# ac_mk2.net
KiCad netlist of a schematic drawn in EAGLE
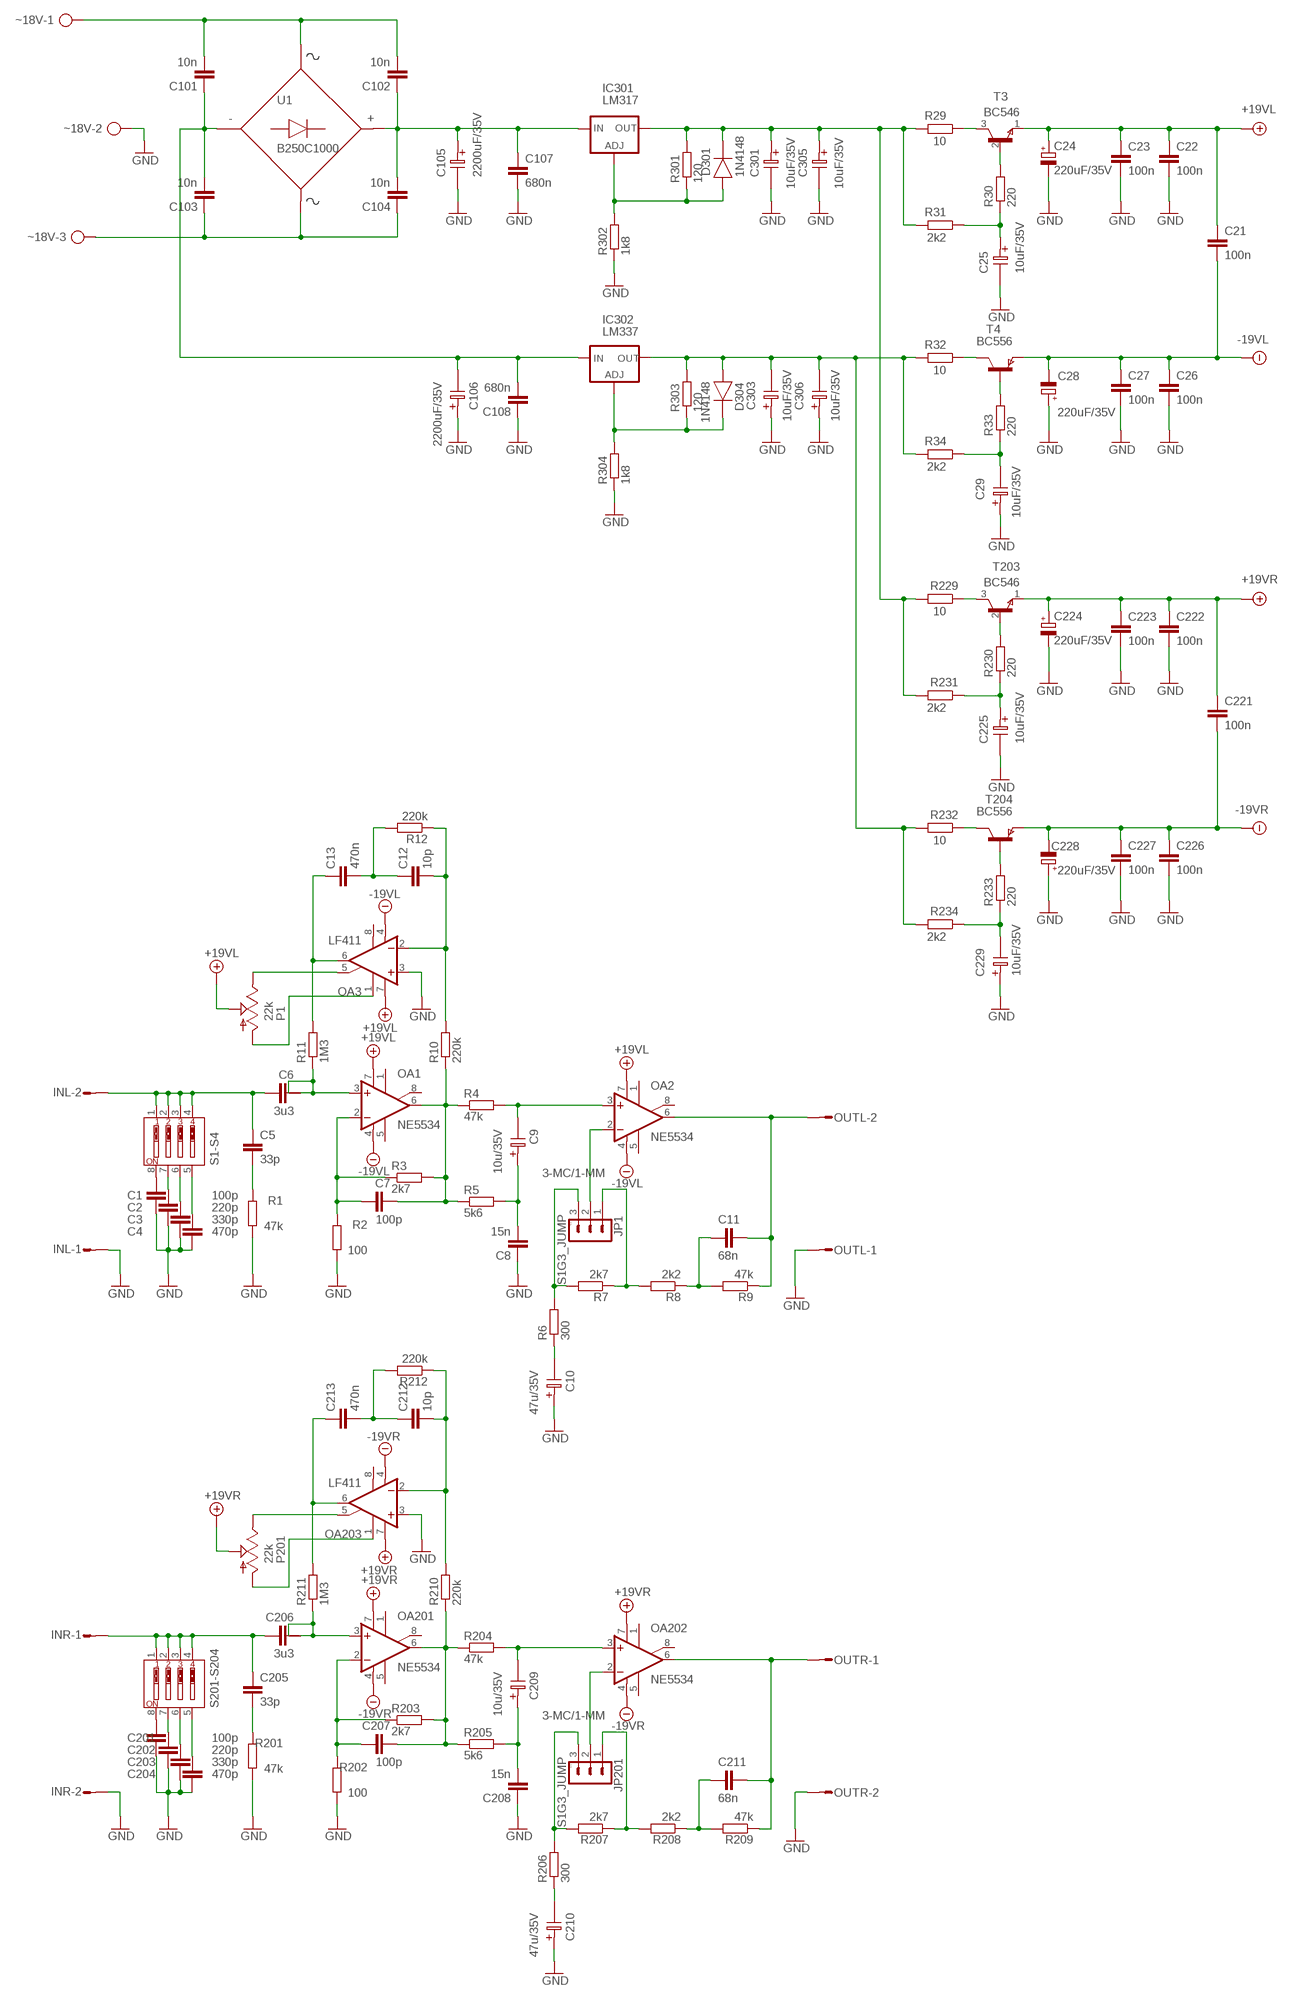
[diagram p0: schematic, sheet 1]

(export (version "E")
  (design (tool "Eeschema 10.0.6"))
  (components
    (comp (ref "C1")
      (value "100p")
      (footprint "eagle-import:C5B3.5")
      (libsource (lib "eagle-import") (part "C5/3.5"))
    )
    (comp (ref "C2")
      (value "220p")
      (footprint "eagle-import:C5B3.5")
      (libsource (lib "eagle-import") (part "C5/3.5"))
    )
    (comp (ref "C3")
      (value "330p")
      (footprint "eagle-import:C5B3.5")
      (libsource (lib "eagle-import") (part "C5/3.5"))
    )
    (comp (ref "C4")
      (value "470p")
      (footprint "eagle-import:C5B3.5")
      (libsource (lib "eagle-import") (part "C5/3.5"))
    )
    (comp (ref "C5")
      (value "33p")
      (footprint "eagle-import:KERAMICKY_RM5")
      (libsource (lib "eagle-import") (part "KERAMICKYRM5"))
    )
    (comp (ref "C6")
      (value "3u3")
      (footprint "eagle-import:C10-15B6")
      (libsource (lib "eagle-import") (part "C-10-15/6"))
    )
    (comp (ref "C7")
      (value "100p")
      (footprint "eagle-import:C5B3.5")
      (libsource (lib "eagle-import") (part "C5/3.5"))
    )
    (comp (ref "C8")
      (value "15n")
      (footprint "eagle-import:C5B3.5")
      (libsource (lib "eagle-import") (part "C5/3.5"))
    )
    (comp (ref "C9")
      (value "10u/35V")
      (footprint "eagle-import:CT07")
      (libsource (lib "eagle-import") (part "CT07"))
    )
    (comp (ref "C10")
      (value "47u/35V")
      (footprint "eagle-import:CT07")
      (libsource (lib "eagle-import") (part "CT07"))
    )
    (comp (ref "C11")
      (value "68n")
      (footprint "eagle-import:C5B3.5")
      (libsource (lib "eagle-import") (part "C5/3.5"))
    )
    (comp (ref "C12")
      (value "10p")
      (footprint "eagle-import:KERAMICKY_RM5")
      (libsource (lib "eagle-import") (part "KERAMICKYRM5"))
    )
    (comp (ref "C13")
      (value "470n")
      (footprint "eagle-import:C5B5.5")
      (libsource (lib "eagle-import") (part "C5/5.5"))
    )
    (comp (ref "C21")
      (value "100n")
      (footprint "eagle-import:C5B3.5")
      (libsource (lib "eagle-import") (part "C5/3.5"))
    )
    (comp (ref "C22")
      (value "100n")
      (footprint "eagle-import:C5B3.5")
      (libsource (lib "eagle-import") (part "C5/3.5"))
    )
    (comp (ref "C23")
      (value "100n")
      (footprint "eagle-import:C5B3.5")
      (libsource (lib "eagle-import") (part "C5/3.5"))
    )
    (comp (ref "C24")
      (value "220uF/35V")
      (footprint "eagle-import:ELEKTROLITICKY_RM3,5-8")
      (libsource (lib "eagle-import") (part "ELEKTROLITICKYRM3,5-8"))
    )
    (comp (ref "C25")
      (value "10uF/35V")
      (footprint "eagle-import:CT07")
      (libsource (lib "eagle-import") (part "CT07"))
    )
    (comp (ref "C26")
      (value "100n")
      (footprint "eagle-import:C5B3.5")
      (libsource (lib "eagle-import") (part "C5/3.5"))
    )
    (comp (ref "C27")
      (value "100n")
      (footprint "eagle-import:C5B3.5")
      (libsource (lib "eagle-import") (part "C5/3.5"))
    )
    (comp (ref "C28")
      (value "220uF/35V")
      (footprint "eagle-import:ELEKTROLITICKY_RM3,5-8")
      (libsource (lib "eagle-import") (part "ELEKTROLITICKYRM3,5-8"))
    )
    (comp (ref "C29")
      (value "10uF/35V")
      (footprint "eagle-import:CT07")
      (libsource (lib "eagle-import") (part "CT07"))
    )
    (comp (ref "C101")
      (value "10n")
      (footprint "eagle-import:C5B3.5")
      (libsource (lib "eagle-import") (part "C5/3.5"))
    )
    (comp (ref "C102")
      (value "10n")
      (footprint "eagle-import:C5B3.5")
      (libsource (lib "eagle-import") (part "C5/3.5"))
    )
    (comp (ref "C103")
      (value "10n")
      (footprint "eagle-import:C5B3.5")
      (libsource (lib "eagle-import") (part "C5/3.5"))
    )
    (comp (ref "C104")
      (value "10n")
      (footprint "eagle-import:C5B3.5")
      (libsource (lib "eagle-import") (part "C5/3.5"))
    )
    (comp (ref "C105")
      (value "2200uF/35V")
      (footprint "eagle-import:E160")
      (libsource (lib "eagle-import") (part "E16X25"))
    )
    (comp (ref "C106")
      (value "2200uF/35V")
      (footprint "eagle-import:E160")
      (libsource (lib "eagle-import") (part "E16X25"))
    )
    (comp (ref "C107")
      (value "680n")
      (footprint "eagle-import:C5B5.5")
      (libsource (lib "eagle-import") (part "C5/5.5"))
    )
    (comp (ref "C108")
      (value "680n")
      (footprint "eagle-import:C5B5.5")
      (libsource (lib "eagle-import") (part "C5/5.5"))
    )
    (comp (ref "C201")
      (value "100p")
      (footprint "eagle-import:C5B3.5")
      (libsource (lib "eagle-import") (part "C5/3.5"))
    )
    (comp (ref "C202")
      (value "220p")
      (footprint "eagle-import:C5B3.5")
      (libsource (lib "eagle-import") (part "C5/3.5"))
    )
    (comp (ref "C203")
      (value "330p")
      (footprint "eagle-import:C5B3.5")
      (libsource (lib "eagle-import") (part "C5/3.5"))
    )
    (comp (ref "C204")
      (value "470p")
      (footprint "eagle-import:C5B3.5")
      (libsource (lib "eagle-import") (part "C5/3.5"))
    )
    (comp (ref "C205")
      (value "33p")
      (footprint "eagle-import:KERAMICKY_RM5")
      (libsource (lib "eagle-import") (part "KERAMICKYRM5"))
    )
    (comp (ref "C206")
      (value "3u3")
      (footprint "eagle-import:C10-15B6")
      (libsource (lib "eagle-import") (part "C-10-15/6"))
    )
    (comp (ref "C207")
      (value "100p")
      (footprint "eagle-import:C5B3.5")
      (libsource (lib "eagle-import") (part "C5/3.5"))
    )
    (comp (ref "C208")
      (value "15n")
      (footprint "eagle-import:C5B3.5")
      (libsource (lib "eagle-import") (part "C5/3.5"))
    )
    (comp (ref "C209")
      (value "10u/35V")
      (footprint "eagle-import:CT07")
      (libsource (lib "eagle-import") (part "CT07"))
    )
    (comp (ref "C210")
      (value "47u/35V")
      (footprint "eagle-import:CT07")
      (libsource (lib "eagle-import") (part "CT07"))
    )
    (comp (ref "C211")
      (value "68n")
      (footprint "eagle-import:C5B3.5")
      (libsource (lib "eagle-import") (part "C5/3.5"))
    )
    (comp (ref "C212")
      (value "10p")
      (footprint "eagle-import:KERAMICKY_RM5")
      (libsource (lib "eagle-import") (part "KERAMICKYRM5"))
    )
    (comp (ref "C213")
      (value "470n")
      (footprint "eagle-import:C5B5.5")
      (libsource (lib "eagle-import") (part "C5/5.5"))
    )
    (comp (ref "C221")
      (value "100n")
      (footprint "eagle-import:C5B3.5")
      (libsource (lib "eagle-import") (part "C5/3.5"))
    )
    (comp (ref "C222")
      (value "100n")
      (footprint "eagle-import:C5B3.5")
      (libsource (lib "eagle-import") (part "C5/3.5"))
    )
    (comp (ref "C223")
      (value "100n")
      (footprint "eagle-import:C5B3.5")
      (libsource (lib "eagle-import") (part "C5/3.5"))
    )
    (comp (ref "C224")
      (value "220uF/35V")
      (footprint "eagle-import:ELEKTROLITICKY_RM3,5-8")
      (libsource (lib "eagle-import") (part "ELEKTROLITICKYRM3,5-8"))
    )
    (comp (ref "C225")
      (value "10uF/35V")
      (footprint "eagle-import:CT07")
      (libsource (lib "eagle-import") (part "CT07"))
    )
    (comp (ref "C226")
      (value "100n")
      (footprint "eagle-import:C5B3.5")
      (libsource (lib "eagle-import") (part "C5/3.5"))
    )
    (comp (ref "C227")
      (value "100n")
      (footprint "eagle-import:C5B3.5")
      (libsource (lib "eagle-import") (part "C5/3.5"))
    )
    (comp (ref "C228")
      (value "220uF/35V")
      (footprint "eagle-import:ELEKTROLITICKY_RM3,5-8")
      (libsource (lib "eagle-import") (part "ELEKTROLITICKYRM3,5-8"))
    )
    (comp (ref "C229")
      (value "10uF/35V")
      (footprint "eagle-import:CT07")
      (libsource (lib "eagle-import") (part "CT07"))
    )
    (comp (ref "C301")
      (value "10uF/35V")
      (footprint "eagle-import:CT07")
      (libsource (lib "eagle-import") (part "CT07"))
    )
    (comp (ref "C303")
      (value "10uF/35V")
      (footprint "eagle-import:CT07")
      (libsource (lib "eagle-import") (part "CT07"))
    )
    (comp (ref "C305")
      (value "10uF/35V")
      (footprint "eagle-import:CT07")
      (libsource (lib "eagle-import") (part "CT07"))
    )
    (comp (ref "C306")
      (value "10uF/35V")
      (footprint "eagle-import:CT07")
      (libsource (lib "eagle-import") (part "CT07"))
    )
    (comp (ref "D301")
      (value "1N4148")
      (footprint "eagle-import:DO41")
      (libsource (lib "eagle-import") (part "1N4148"))
    )
    (comp (ref "D304")
      (value "1N4148")
      (footprint "eagle-import:DO41")
      (libsource (lib "eagle-import") (part "1N4148"))
    )
    (comp (ref "IC301")
      (value "LM317")
      (footprint "eagle-import:317TS")
      (libsource (lib "eagle-import") (part "LM317TS"))
    )
    (comp (ref "IC302")
      (value "LM337")
      (footprint "eagle-import:337TS")
      (libsource (lib "eagle-import") (part "LM337TS"))
    )
    (comp (ref "INL")
      (value "S02P")
      (footprint "eagle-import:S02P")
      (libsource (lib "eagle-import") (part "S02P"))
    )
    (comp (ref "INR")
      (value "S02P")
      (footprint "eagle-import:S02P")
      (libsource (lib "eagle-import") (part "S02P"))
    )
    (comp (ref "JP1")
      (value "S1G3_JUMP")
      (footprint "eagle-import:S1G3_JUM")
      (libsource (lib "eagle-import") (part "S1G3_JUMP"))
    )
    (comp (ref "JP201")
      (value "S1G3_JUMP")
      (footprint "eagle-import:S1G3_JUM")
      (libsource (lib "eagle-import") (part "S1G3_JUMP"))
    )
    (comp (ref "OA1")
      (value "NE5534")
      (footprint "eagle-import:DIL08")
      (libsource (lib "eagle-import") (part "NE5534N"))
    )
    (comp (ref "OA2")
      (value "NE5534")
      (footprint "eagle-import:DIL08")
      (libsource (lib "eagle-import") (part "NE5534N"))
    )
    (comp (ref "OA3")
      (value "LF411")
      (footprint "eagle-import:DIL08")
      (libsource (lib "eagle-import") (part "LF411N"))
    )
    (comp (ref "OA201")
      (value "NE5534")
      (footprint "eagle-import:DIL08")
      (libsource (lib "eagle-import") (part "NE5534N"))
    )
    (comp (ref "OA202")
      (value "NE5534")
      (footprint "eagle-import:DIL08")
      (libsource (lib "eagle-import") (part "NE5534N"))
    )
    (comp (ref "OA203")
      (value "LF411")
      (footprint "eagle-import:DIL08")
      (libsource (lib "eagle-import") (part "LF411N"))
    )
    (comp (ref "OUTL")
      (value "S02P")
      (footprint "eagle-import:S02P")
      (libsource (lib "eagle-import") (part "S02P"))
    )
    (comp (ref "OUTR")
      (value "S02P")
      (footprint "eagle-import:S02P")
      (libsource (lib "eagle-import") (part "S02P"))
    )
    (comp (ref "P1")
      (value "22k")
      (footprint "eagle-import:S64W")
      (libsource (lib "eagle-import") (part "TRIM_US-S64W"))
    )
    (comp (ref "P201")
      (value "22k")
      (footprint "eagle-import:S64W")
      (libsource (lib "eagle-import") (part "TRIM_US-S64W"))
    )
    (comp (ref "R1")
      (value "47k")
      (footprint "eagle-import:0207_10")
      (libsource (lib "eagle-import") (part "R-EU_0207/10"))
    )
    (comp (ref "R2")
      (value "100")
      (footprint "eagle-import:0207_10")
      (libsource (lib "eagle-import") (part "R-EU_0207/10"))
    )
    (comp (ref "R3")
      (value "2k7")
      (footprint "eagle-import:0207_10")
      (libsource (lib "eagle-import") (part "R-EU_0207/10"))
    )
    (comp (ref "R4")
      (value "47k")
      (footprint "eagle-import:0207_10")
      (libsource (lib "eagle-import") (part "R-EU_0207/10"))
    )
    (comp (ref "R5")
      (value "5k6")
      (footprint "eagle-import:0207_10")
      (libsource (lib "eagle-import") (part "R-EU_0207/10"))
    )
    (comp (ref "R6")
      (value "300")
      (footprint "eagle-import:0207_10")
      (libsource (lib "eagle-import") (part "R-EU_0207/10"))
    )
    (comp (ref "R7")
      (value "2k7")
      (footprint "eagle-import:0207_10")
      (libsource (lib "eagle-import") (part "R-EU_0207/10"))
    )
    (comp (ref "R8")
      (value "2k2")
      (footprint "eagle-import:0207_10")
      (libsource (lib "eagle-import") (part "R-EU_0207/10"))
    )
    (comp (ref "R9")
      (value "47k")
      (footprint "eagle-import:0207_10")
      (libsource (lib "eagle-import") (part "R-EU_0207/10"))
    )
    (comp (ref "R10")
      (value "220k")
      (footprint "eagle-import:0207_10")
      (libsource (lib "eagle-import") (part "R-EU_0207/10"))
    )
    (comp (ref "R11")
      (value "1M3")
      (footprint "eagle-import:0207_10")
      (libsource (lib "eagle-import") (part "R-EU_0207/10"))
    )
    (comp (ref "R12")
      (value "220k")
      (footprint "eagle-import:0207_10")
      (libsource (lib "eagle-import") (part "R-EU_0207/10"))
    )
    (comp (ref "R29")
      (value "10")
      (footprint "eagle-import:0207_10")
      (libsource (lib "eagle-import") (part "R-EU_0207/10"))
    )
    (comp (ref "R30")
      (value "220")
      (footprint "eagle-import:0207_10")
      (libsource (lib "eagle-import") (part "R-EU_0207/10"))
    )
    (comp (ref "R31")
      (value "2k2")
      (footprint "eagle-import:0207_10")
      (libsource (lib "eagle-import") (part "R-EU_0207/10"))
    )
    (comp (ref "R32")
      (value "10")
      (footprint "eagle-import:0207_10")
      (libsource (lib "eagle-import") (part "R-EU_0207/10"))
    )
    (comp (ref "R33")
      (value "220")
      (footprint "eagle-import:0207_10")
      (libsource (lib "eagle-import") (part "R-EU_0207/10"))
    )
    (comp (ref "R34")
      (value "2k2")
      (footprint "eagle-import:0207_10")
      (libsource (lib "eagle-import") (part "R-EU_0207/10"))
    )
    (comp (ref "R201")
      (value "47k")
      (footprint "eagle-import:0207_10")
      (libsource (lib "eagle-import") (part "R-EU_0207/10"))
    )
    (comp (ref "R202")
      (value "100")
      (footprint "eagle-import:0207_10")
      (libsource (lib "eagle-import") (part "R-EU_0207/10"))
    )
    (comp (ref "R203")
      (value "2k7")
      (footprint "eagle-import:0207_10")
      (libsource (lib "eagle-import") (part "R-EU_0207/10"))
    )
    (comp (ref "R204")
      (value "47k")
      (footprint "eagle-import:0207_10")
      (libsource (lib "eagle-import") (part "R-EU_0207/10"))
    )
    (comp (ref "R205")
      (value "5k6")
      (footprint "eagle-import:0207_10")
      (libsource (lib "eagle-import") (part "R-EU_0207/10"))
    )
    (comp (ref "R206")
      (value "300")
      (footprint "eagle-import:0207_10")
      (libsource (lib "eagle-import") (part "R-EU_0207/10"))
    )
    (comp (ref "R207")
      (value "2k7")
      (footprint "eagle-import:0207_10")
      (libsource (lib "eagle-import") (part "R-EU_0207/10"))
    )
    (comp (ref "R208")
      (value "2k2")
      (footprint "eagle-import:0207_10")
      (libsource (lib "eagle-import") (part "R-EU_0207/10"))
    )
    (comp (ref "R209")
      (value "47k")
      (footprint "eagle-import:0207_10")
      (libsource (lib "eagle-import") (part "R-EU_0207/10"))
    )
    (comp (ref "R210")
      (value "220k")
      (footprint "eagle-import:0207_10")
      (libsource (lib "eagle-import") (part "R-EU_0207/10"))
    )
    (comp (ref "R211")
      (value "1M3")
      (footprint "eagle-import:0207_10")
      (libsource (lib "eagle-import") (part "R-EU_0207/10"))
    )
    (comp (ref "R212")
      (value "220k")
      (footprint "eagle-import:0207_10")
      (libsource (lib "eagle-import") (part "R-EU_0207/10"))
    )
    (comp (ref "R229")
      (value "10")
      (footprint "eagle-import:0207_10")
      (libsource (lib "eagle-import") (part "R-EU_0207/10"))
    )
    (comp (ref "R230")
      (value "220")
      (footprint "eagle-import:0207_10")
      (libsource (lib "eagle-import") (part "R-EU_0207/10"))
    )
    (comp (ref "R231")
      (value "2k2")
      (footprint "eagle-import:0207_10")
      (libsource (lib "eagle-import") (part "R-EU_0207/10"))
    )
    (comp (ref "R232")
      (value "10")
      (footprint "eagle-import:0207_10")
      (libsource (lib "eagle-import") (part "R-EU_0207/10"))
    )
    (comp (ref "R233")
      (value "220")
      (footprint "eagle-import:0207_10")
      (libsource (lib "eagle-import") (part "R-EU_0207/10"))
    )
    (comp (ref "R234")
      (value "2k2")
      (footprint "eagle-import:0207_10")
      (libsource (lib "eagle-import") (part "R-EU_0207/10"))
    )
    (comp (ref "R301")
      (value "120")
      (footprint "eagle-import:0207_10")
      (libsource (lib "eagle-import") (part "R-EU_0207/10"))
    )
    (comp (ref "R302")
      (value "1k8")
      (footprint "eagle-import:0207_10")
      (libsource (lib "eagle-import") (part "R-EU_0207/10"))
    )
    (comp (ref "R303")
      (value "120")
      (footprint "eagle-import:0207_10")
      (libsource (lib "eagle-import") (part "R-EU_0207/10"))
    )
    (comp (ref "R304")
      (value "1k8")
      (footprint "eagle-import:0207_10")
      (libsource (lib "eagle-import") (part "R-EU_0207/10"))
    )
    (comp (ref "S1-S4")
      (value "DIP4X")
      (footprint "eagle-import:EDG-04")
      (libsource (lib "eagle-import") (part "DIP4X"))
    )
    (comp (ref "S201-S204")
      (value "DIP4X")
      (footprint "eagle-import:EDG-04")
      (libsource (lib "eagle-import") (part "DIP4X"))
    )
    (comp (ref "T3")
      (value "BC546")
      (footprint "eagle-import:TO-92C")
      (libsource (lib "eagle-import") (part "BC546A"))
    )
    (comp (ref "T4")
      (value "BC556")
      (footprint "eagle-import:TO-92C")
      (libsource (lib "eagle-import") (part "BC556B"))
    )
    (comp (ref "T203")
      (value "BC546")
      (footprint "eagle-import:TO-92C")
      (libsource (lib "eagle-import") (part "BC546A"))
    )
    (comp (ref "T204")
      (value "BC556")
      (footprint "eagle-import:TO-92C")
      (libsource (lib "eagle-import") (part "BC556B"))
    )
    (comp (ref "U1")
      (value "B250C1000")
      (footprint "eagle-import:DB1")
      (libsource (lib "eagle-import") (part "B250C1500"))
    )
    (comp (ref "~18V")
      (value "AK500/3")
      (footprint "eagle-import:AK500_3")
      (libsource (lib "eagle-import") (part "AK500/3"))
    )
  )
  (nets
    (net (code "1") (name "+19VL") (class "Default")
      (node (ref "C21") (pin "1") (pinfunction "1_1") (pintype "passive"))
      (node (ref "C22") (pin "1") (pinfunction "1_1") (pintype "passive"))
      (node (ref "C23") (pin "1") (pinfunction "1_1") (pintype "passive"))
      (node (ref "C24") (pin "P$2") (pinfunction "+_P$2") (pintype "passive"))
      (node (ref "OA1") (pin "7") (pinfunction "V+_7") (pintype "power_in"))
      (node (ref "OA2") (pin "7") (pinfunction "V+_7") (pintype "power_in"))
      (node (ref "OA3") (pin "7") (pinfunction "V+_7") (pintype "power_in"))
      (node (ref "P1") (pin "S") (pinfunction "S_S") (pintype "passive"))
      (node (ref "T3") (pin "1") (pinfunction "E_1") (pintype "passive"))
    )
    (net (code "2") (name "+19VR") (class "Default")
      (node (ref "C221") (pin "1") (pinfunction "1_1") (pintype "passive"))
      (node (ref "C222") (pin "1") (pinfunction "1_1") (pintype "passive"))
      (node (ref "C223") (pin "1") (pinfunction "1_1") (pintype "passive"))
      (node (ref "C224") (pin "P$2") (pinfunction "+_P$2") (pintype "passive"))
      (node (ref "OA201") (pin "7") (pinfunction "V+_7") (pintype "power_in"))
      (node (ref "OA202") (pin "7") (pinfunction "V+_7") (pintype "power_in"))
      (node (ref "OA203") (pin "7") (pinfunction "V+_7") (pintype "power_in"))
      (node (ref "P201") (pin "S") (pinfunction "S_S") (pintype "passive"))
      (node (ref "T203") (pin "1") (pinfunction "E_1") (pintype "passive"))
    )
    (net (code "3") (name "-19VL") (class "Default")
      (node (ref "C21") (pin "2") (pinfunction "2_2") (pintype "passive"))
      (node (ref "C26") (pin "1") (pinfunction "1_1") (pintype "passive"))
      (node (ref "C27") (pin "1") (pinfunction "1_1") (pintype "passive"))
      (node (ref "C28") (pin "P$1") (pinfunction "-_P$1") (pintype "passive"))
      (node (ref "OA1") (pin "4") (pinfunction "V-_4") (pintype "power_in"))
      (node (ref "OA2") (pin "4") (pinfunction "V-_4") (pintype "power_in"))
      (node (ref "OA3") (pin "4") (pinfunction "V-_4") (pintype "power_in"))
      (node (ref "T4") (pin "1") (pinfunction "E_1") (pintype "passive"))
    )
    (net (code "4") (name "-19VR") (class "Default")
      (node (ref "C221") (pin "2") (pinfunction "2_2") (pintype "passive"))
      (node (ref "C226") (pin "1") (pinfunction "1_1") (pintype "passive"))
      (node (ref "C227") (pin "1") (pinfunction "1_1") (pintype "passive"))
      (node (ref "C228") (pin "P$1") (pinfunction "-_P$1") (pintype "passive"))
      (node (ref "OA201") (pin "4") (pinfunction "V-_4") (pintype "power_in"))
      (node (ref "OA202") (pin "4") (pinfunction "V-_4") (pintype "power_in"))
      (node (ref "OA203") (pin "4") (pinfunction "V-_4") (pintype "power_in"))
      (node (ref "T204") (pin "1") (pinfunction "E_1") (pintype "passive"))
    )
    (net (code "5") (name "GND") (class "Default")
      (node (ref "C1") (pin "2") (pinfunction "2_2") (pintype "passive"))
      (node (ref "C10") (pin "1") (pinfunction "1_1") (pintype "passive"))
      (node (ref "C105") (pin "2") (pinfunction "2_2") (pintype "passive"))
      (node (ref "C106") (pin "1") (pinfunction "1_1") (pintype "passive"))
      (node (ref "C107") (pin "2") (pinfunction "2_2") (pintype "passive"))
      (node (ref "C108") (pin "1") (pinfunction "1_1") (pintype "passive"))
      (node (ref "C2") (pin "2") (pinfunction "2_2") (pintype "passive"))
      (node (ref "C201") (pin "2") (pinfunction "2_2") (pintype "passive"))
      (node (ref "C202") (pin "2") (pinfunction "2_2") (pintype "passive"))
      (node (ref "C203") (pin "2") (pinfunction "2_2") (pintype "passive"))
      (node (ref "C204") (pin "2") (pinfunction "2_2") (pintype "passive"))
      (node (ref "C208") (pin "1") (pinfunction "1_1") (pintype "passive"))
      (node (ref "C210") (pin "1") (pinfunction "1_1") (pintype "passive"))
      (node (ref "C22") (pin "2") (pinfunction "2_2") (pintype "passive"))
      (node (ref "C222") (pin "2") (pinfunction "2_2") (pintype "passive"))
      (node (ref "C223") (pin "2") (pinfunction "2_2") (pintype "passive"))
      (node (ref "C224") (pin "P$1") (pinfunction "-_P$1") (pintype "passive"))
      (node (ref "C225") (pin "2") (pinfunction "2_2") (pintype "passive"))
      (node (ref "C226") (pin "2") (pinfunction "2_2") (pintype "passive"))
      (node (ref "C227") (pin "2") (pinfunction "2_2") (pintype "passive"))
      (node (ref "C228") (pin "P$2") (pinfunction "+_P$2") (pintype "passive"))
      (node (ref "C229") (pin "1") (pinfunction "1_1") (pintype "passive"))
      (node (ref "C23") (pin "2") (pinfunction "2_2") (pintype "passive"))
      (node (ref "C24") (pin "P$1") (pinfunction "-_P$1") (pintype "passive"))
      (node (ref "C25") (pin "2") (pinfunction "2_2") (pintype "passive"))
      (node (ref "C26") (pin "2") (pinfunction "2_2") (pintype "passive"))
      (node (ref "C27") (pin "2") (pinfunction "2_2") (pintype "passive"))
      (node (ref "C28") (pin "P$2") (pinfunction "+_P$2") (pintype "passive"))
      (node (ref "C29") (pin "1") (pinfunction "1_1") (pintype "passive"))
      (node (ref "C3") (pin "2") (pinfunction "2_2") (pintype "passive"))
      (node (ref "C301") (pin "2") (pinfunction "2_2") (pintype "passive"))
      (node (ref "C303") (pin "1") (pinfunction "1_1") (pintype "passive"))
      (node (ref "C305") (pin "2") (pinfunction "2_2") (pintype "passive"))
      (node (ref "C306") (pin "1") (pinfunction "1_1") (pintype "passive"))
      (node (ref "C4") (pin "2") (pinfunction "2_2") (pintype "passive"))
      (node (ref "C8") (pin "1") (pinfunction "1_1") (pintype "passive"))
      (node (ref "INL") (pin "1") (pinfunction "S_1") (pintype "passive"))
      (node (ref "INR") (pin "2") (pinfunction "S_2") (pintype "passive"))
      (node (ref "OA203") (pin "3") (pinfunction "+IN_3") (pintype "input"))
      (node (ref "OA3") (pin "3") (pinfunction "+IN_3") (pintype "input"))
      (node (ref "OUTL") (pin "1") (pinfunction "S_1") (pintype "passive"))
      (node (ref "OUTR") (pin "2") (pinfunction "S_2") (pintype "passive"))
      (node (ref "R1") (pin "1") (pinfunction "1_1") (pintype "passive"))
      (node (ref "R2") (pin "1") (pinfunction "1_1") (pintype "passive"))
      (node (ref "R201") (pin "1") (pinfunction "1_1") (pintype "passive"))
      (node (ref "R202") (pin "1") (pinfunction "1_1") (pintype "passive"))
      (node (ref "R302") (pin "1") (pinfunction "1_1") (pintype "passive"))
      (node (ref "R304") (pin "1") (pinfunction "1_1") (pintype "passive"))
      (node (ref "~18V") (pin "2") (pinfunction "KL_2") (pintype "passive"))
    )
    (net (code "6") (name "Net-(C1-Pad1)") (class "Default")
      (node (ref "C1") (pin "1") (pinfunction "1_1") (pintype "passive"))
      (node (ref "S1-S4") (pin "8") (pinfunction "8_8") (pintype "passive"))
    )
    (net (code "7") (name "Net-(C2-Pad1)") (class "Default")
      (node (ref "C2") (pin "1") (pinfunction "1_1") (pintype "passive"))
      (node (ref "S1-S4") (pin "7") (pinfunction "7_7") (pintype "passive"))
    )
    (net (code "8") (name "Net-(C3-Pad1)") (class "Default")
      (node (ref "C3") (pin "1") (pinfunction "1_1") (pintype "passive"))
      (node (ref "S1-S4") (pin "6") (pinfunction "6_6") (pintype "passive"))
    )
    (net (code "9") (name "Net-(C4-Pad1)") (class "Default")
      (node (ref "C4") (pin "1") (pinfunction "1_1") (pintype "passive"))
      (node (ref "S1-S4") (pin "5") (pinfunction "5_5") (pintype "passive"))
    )
    (net (code "10") (name "Net-(C5-1)") (class "Default")
      (node (ref "C5") (pin "P$1") (pinfunction "1_P$1") (pintype "passive"))
      (node (ref "C6") (pin "1") (pinfunction "1_1") (pintype "passive"))
      (node (ref "INL") (pin "2") (pinfunction "S_2") (pintype "passive"))
      (node (ref "S1-S4") (pin "1") (pinfunction "1_1") (pintype "passive"))
      (node (ref "S1-S4") (pin "2") (pinfunction "2_2") (pintype "passive"))
      (node (ref "S1-S4") (pin "3") (pinfunction "3_3") (pintype "passive"))
      (node (ref "S1-S4") (pin "4") (pinfunction "4_4") (pintype "passive"))
    )
    (net (code "11") (name "Net-(C5-2)") (class "Default")
      (node (ref "C5") (pin "P$2") (pinfunction "2_P$2") (pintype "passive"))
      (node (ref "R1") (pin "2") (pinfunction "2_2") (pintype "passive"))
    )
    (net (code "12") (name "Net-(C8-Pad2)") (class "Default")
      (node (ref "C8") (pin "2") (pinfunction "2_2") (pintype "passive"))
      (node (ref "C9") (pin "1") (pinfunction "1_1") (pintype "passive"))
      (node (ref "R5") (pin "2") (pinfunction "2_2") (pintype "passive"))
    )
    (net (code "13") (name "Net-(C10-Pad2)") (class "Default")
      (node (ref "C10") (pin "2") (pinfunction "2_2") (pintype "passive"))
      (node (ref "R6") (pin "1") (pinfunction "1_1") (pintype "passive"))
    )
    (net (code "14") (name "Net-(C11-Pad2)") (class "Default")
      (node (ref "C11") (pin "2") (pinfunction "2_2") (pintype "passive"))
      (node (ref "R8") (pin "1") (pinfunction "1_1") (pintype "passive"))
      (node (ref "R9") (pin "2") (pinfunction "2_2") (pintype "passive"))
    )
    (net (code "15") (name "Net-(C12-1)") (class "Default")
      (node (ref "C12") (pin "P$1") (pinfunction "1_P$1") (pintype "passive"))
      (node (ref "C13") (pin "2") (pinfunction "2_2") (pintype "passive"))
      (node (ref "R12") (pin "2") (pinfunction "2_2") (pintype "passive"))
    )
    (net (code "16") (name "Net-(C12-2)") (class "Default")
      (node (ref "C12") (pin "P$2") (pinfunction "2_P$2") (pintype "passive"))
      (node (ref "OA3") (pin "2") (pinfunction "-IN_2") (pintype "input"))
      (node (ref "R10") (pin "2") (pinfunction "2_2") (pintype "passive"))
      (node (ref "R12") (pin "1") (pinfunction "1_1") (pintype "passive"))
    )
    (net (code "17") (name "Net-(C25-Pad1)") (class "Default")
      (node (ref "C25") (pin "1") (pinfunction "1_1") (pintype "passive"))
      (node (ref "R30") (pin "1") (pinfunction "1_1") (pintype "passive"))
      (node (ref "R31") (pin "1") (pinfunction "1_1") (pintype "passive"))
    )
    (net (code "18") (name "Net-(C29-Pad2)") (class "Default")
      (node (ref "C29") (pin "2") (pinfunction "2_2") (pintype "passive"))
      (node (ref "R33") (pin "1") (pinfunction "1_1") (pintype "passive"))
      (node (ref "R34") (pin "1") (pinfunction "1_1") (pintype "passive"))
    )
    (net (code "19") (name "Net-(C201-Pad1)") (class "Default")
      (node (ref "C201") (pin "1") (pinfunction "1_1") (pintype "passive"))
      (node (ref "S201-S204") (pin "8") (pinfunction "8_8") (pintype "passive"))
    )
    (net (code "20") (name "Net-(C202-Pad1)") (class "Default")
      (node (ref "C202") (pin "1") (pinfunction "1_1") (pintype "passive"))
      (node (ref "S201-S204") (pin "7") (pinfunction "7_7") (pintype "passive"))
    )
    (net (code "21") (name "Net-(C203-Pad1)") (class "Default")
      (node (ref "C203") (pin "1") (pinfunction "1_1") (pintype "passive"))
      (node (ref "S201-S204") (pin "6") (pinfunction "6_6") (pintype "passive"))
    )
    (net (code "22") (name "Net-(C204-Pad1)") (class "Default")
      (node (ref "C204") (pin "1") (pinfunction "1_1") (pintype "passive"))
      (node (ref "S201-S204") (pin "5") (pinfunction "5_5") (pintype "passive"))
    )
    (net (code "23") (name "Net-(C205-1)") (class "Default")
      (node (ref "C205") (pin "P$1") (pinfunction "1_P$1") (pintype "passive"))
      (node (ref "C206") (pin "1") (pinfunction "1_1") (pintype "passive"))
      (node (ref "INR") (pin "1") (pinfunction "S_1") (pintype "passive"))
      (node (ref "S201-S204") (pin "1") (pinfunction "1_1") (pintype "passive"))
      (node (ref "S201-S204") (pin "2") (pinfunction "2_2") (pintype "passive"))
      (node (ref "S201-S204") (pin "3") (pinfunction "3_3") (pintype "passive"))
      (node (ref "S201-S204") (pin "4") (pinfunction "4_4") (pintype "passive"))
    )
    (net (code "24") (name "Net-(C205-2)") (class "Default")
      (node (ref "C205") (pin "P$2") (pinfunction "2_P$2") (pintype "passive"))
      (node (ref "R201") (pin "2") (pinfunction "2_2") (pintype "passive"))
    )
    (net (code "25") (name "Net-(C208-Pad2)") (class "Default")
      (node (ref "C208") (pin "2") (pinfunction "2_2") (pintype "passive"))
      (node (ref "C209") (pin "1") (pinfunction "1_1") (pintype "passive"))
      (node (ref "R205") (pin "2") (pinfunction "2_2") (pintype "passive"))
    )
    (net (code "26") (name "Net-(C210-Pad2)") (class "Default")
      (node (ref "C210") (pin "2") (pinfunction "2_2") (pintype "passive"))
      (node (ref "R206") (pin "1") (pinfunction "1_1") (pintype "passive"))
    )
    (net (code "27") (name "Net-(C211-Pad2)") (class "Default")
      (node (ref "C211") (pin "2") (pinfunction "2_2") (pintype "passive"))
      (node (ref "R208") (pin "1") (pinfunction "1_1") (pintype "passive"))
      (node (ref "R209") (pin "2") (pinfunction "2_2") (pintype "passive"))
    )
    (net (code "28") (name "Net-(C212-1)") (class "Default")
      (node (ref "C212") (pin "P$1") (pinfunction "1_P$1") (pintype "passive"))
      (node (ref "C213") (pin "2") (pinfunction "2_2") (pintype "passive"))
      (node (ref "R212") (pin "2") (pinfunction "2_2") (pintype "passive"))
    )
    (net (code "29") (name "Net-(C212-2)") (class "Default")
      (node (ref "C212") (pin "P$2") (pinfunction "2_P$2") (pintype "passive"))
      (node (ref "OA203") (pin "2") (pinfunction "-IN_2") (pintype "input"))
      (node (ref "R210") (pin "2") (pinfunction "2_2") (pintype "passive"))
      (node (ref "R212") (pin "1") (pinfunction "1_1") (pintype "passive"))
    )
    (net (code "30") (name "Net-(C225-Pad1)") (class "Default")
      (node (ref "C225") (pin "1") (pinfunction "1_1") (pintype "passive"))
      (node (ref "R230") (pin "1") (pinfunction "1_1") (pintype "passive"))
      (node (ref "R231") (pin "1") (pinfunction "1_1") (pintype "passive"))
    )
    (net (code "31") (name "Net-(C229-Pad2)") (class "Default")
      (node (ref "C229") (pin "2") (pinfunction "2_2") (pintype "passive"))
      (node (ref "R233") (pin "1") (pinfunction "1_1") (pintype "passive"))
      (node (ref "R234") (pin "1") (pinfunction "1_1") (pintype "passive"))
    )
    (net (code "32") (name "Net-(IC301-ADJ)") (class "Default")
      (node (ref "D301") (pin "A") (pinfunction "A_A") (pintype "passive"))
      (node (ref "IC301") (pin "1") (pinfunction "ADJ_1") (pintype "input"))
      (node (ref "R301") (pin "1") (pinfunction "1_1") (pintype "passive"))
      (node (ref "R302") (pin "2") (pinfunction "2_2") (pintype "passive"))
    )
    (net (code "33") (name "Net-(IC301-IN)") (class "Default")
      (node (ref "C102") (pin "1") (pinfunction "1_1") (pintype "passive"))
      (node (ref "C104") (pin "2") (pinfunction "2_2") (pintype "passive"))
      (node (ref "C105") (pin "1") (pinfunction "1_1") (pintype "passive"))
      (node (ref "C107") (pin "1") (pinfunction "1_1") (pintype "passive"))
      (node (ref "IC301") (pin "3") (pinfunction "IN_3") (pintype "input"))
      (node (ref "U1") (pin "1") (pinfunction "1_1") (pintype "passive"))
    )
    (net (code "34") (name "Net-(IC301-OUT)") (class "Default")
      (node (ref "C301") (pin "1") (pinfunction "1_1") (pintype "passive"))
      (node (ref "C305") (pin "1") (pinfunction "1_1") (pintype "passive"))
      (node (ref "D301") (pin "K") (pinfunction "K_K") (pintype "passive"))
      (node (ref "IC301") (pin "2") (pinfunction "OUT_2") (pintype "passive"))
      (node (ref "R229") (pin "2") (pinfunction "2_2") (pintype "passive"))
      (node (ref "R231") (pin "2") (pinfunction "2_2") (pintype "passive"))
      (node (ref "R29") (pin "2") (pinfunction "2_2") (pintype "passive"))
      (node (ref "R301") (pin "2") (pinfunction "2_2") (pintype "passive"))
      (node (ref "R31") (pin "2") (pinfunction "2_2") (pintype "passive"))
    )
    (net (code "35") (name "Net-(IC302-ADJ)") (class "Default")
      (node (ref "D304") (pin "K") (pinfunction "K_K") (pintype "passive"))
      (node (ref "IC302") (pin "1") (pinfunction "ADJ_1") (pintype "input"))
      (node (ref "R303") (pin "1") (pinfunction "1_1") (pintype "passive"))
      (node (ref "R304") (pin "2") (pinfunction "2_2") (pintype "passive"))
    )
    (net (code "36") (name "Net-(IC302-IN)") (class "Default")
      (node (ref "C101") (pin "1") (pinfunction "1_1") (pintype "passive"))
      (node (ref "C103") (pin "2") (pinfunction "2_2") (pintype "passive"))
      (node (ref "C106") (pin "2") (pinfunction "2_2") (pintype "passive"))
      (node (ref "C108") (pin "2") (pinfunction "2_2") (pintype "passive"))
      (node (ref "IC302") (pin "2") (pinfunction "IN_2") (pintype "input"))
      (node (ref "U1") (pin "2") (pinfunction "2_2") (pintype "passive"))
    )
    (net (code "37") (name "Net-(IC302-OUT)") (class "Default")
      (node (ref "C303") (pin "2") (pinfunction "2_2") (pintype "passive"))
      (node (ref "C306") (pin "2") (pinfunction "2_2") (pintype "passive"))
      (node (ref "D304") (pin "A") (pinfunction "A_A") (pintype "passive"))
      (node (ref "IC302") (pin "3") (pinfunction "OUT_3") (pintype "passive"))
      (node (ref "R232") (pin "2") (pinfunction "2_2") (pintype "passive"))
      (node (ref "R234") (pin "2") (pinfunction "2_2") (pintype "passive"))
      (node (ref "R303") (pin "2") (pinfunction "2_2") (pintype "passive"))
      (node (ref "R32") (pin "2") (pinfunction "2_2") (pintype "passive"))
      (node (ref "R34") (pin "2") (pinfunction "2_2") (pintype "passive"))
    )
    (net (code "38") (name "Net-(JP1-Pad1)") (class "Default")
      (node (ref "JP1") (pin "1") (pinfunction "1_1") (pintype "passive"))
      (node (ref "R7") (pin "1") (pinfunction "1_1") (pintype "passive"))
      (node (ref "R8") (pin "2") (pinfunction "2_2") (pintype "passive"))
    )
    (net (code "39") (name "Net-(JP1-Pad3)") (class "Default")
      (node (ref "JP1") (pin "3") (pinfunction "3_3") (pintype "passive"))
      (node (ref "R6") (pin "2") (pinfunction "2_2") (pintype "passive"))
      (node (ref "R7") (pin "2") (pinfunction "2_2") (pintype "passive"))
    )
    (net (code "40") (name "Net-(JP201-Pad1)") (class "Default")
      (node (ref "JP201") (pin "1") (pinfunction "1_1") (pintype "passive"))
      (node (ref "R207") (pin "1") (pinfunction "1_1") (pintype "passive"))
      (node (ref "R208") (pin "2") (pinfunction "2_2") (pintype "passive"))
    )
    (net (code "41") (name "Net-(JP201-Pad3)") (class "Default")
      (node (ref "JP201") (pin "3") (pinfunction "3_3") (pintype "passive"))
      (node (ref "R206") (pin "2") (pinfunction "2_2") (pintype "passive"))
      (node (ref "R207") (pin "2") (pinfunction "2_2") (pintype "passive"))
    )
    (net (code "42") (name "Net-(OA1-+IN)") (class "Default")
      (node (ref "C6") (pin "2") (pinfunction "2_2") (pintype "passive"))
      (node (ref "C6") (pin "3") (pinfunction "3_3") (pintype "passive"))
      (node (ref "OA1") (pin "3") (pinfunction "+IN_3") (pintype "input"))
      (node (ref "R11") (pin "1") (pinfunction "1_1") (pintype "passive"))
    )
    (net (code "43") (name "Net-(OA1--IN)") (class "Default")
      (node (ref "C7") (pin "1") (pinfunction "1_1") (pintype "passive"))
      (node (ref "OA1") (pin "2") (pinfunction "-IN_2") (pintype "input"))
      (node (ref "R2") (pin "2") (pinfunction "2_2") (pintype "passive"))
      (node (ref "R3") (pin "1") (pinfunction "1_1") (pintype "passive"))
    )
    (net (code "44") (name "Net-(OA1-OUT)") (class "Default")
      (node (ref "C7") (pin "2") (pinfunction "2_2") (pintype "passive"))
      (node (ref "OA1") (pin "6") (pinfunction "OUT_6") (pintype "output"))
      (node (ref "R10") (pin "1") (pinfunction "1_1") (pintype "passive"))
      (node (ref "R3") (pin "2") (pinfunction "2_2") (pintype "passive"))
      (node (ref "R4") (pin "1") (pinfunction "1_1") (pintype "passive"))
      (node (ref "R5") (pin "1") (pinfunction "1_1") (pintype "passive"))
    )
    (net (code "45") (name "Net-(OA2-+IN)") (class "Default")
      (node (ref "C9") (pin "2") (pinfunction "2_2") (pintype "passive"))
      (node (ref "OA2") (pin "3") (pinfunction "+IN_3") (pintype "input"))
      (node (ref "R4") (pin "2") (pinfunction "2_2") (pintype "passive"))
    )
    (net (code "46") (name "Net-(OA2--IN)") (class "Default")
      (node (ref "JP1") (pin "2") (pinfunction "2_2") (pintype "passive"))
      (node (ref "OA2") (pin "2") (pinfunction "-IN_2") (pintype "input"))
    )
    (net (code "47") (name "Net-(OA2-OUT)") (class "Default")
      (node (ref "C11") (pin "1") (pinfunction "1_1") (pintype "passive"))
      (node (ref "OA2") (pin "6") (pinfunction "OUT_6") (pintype "output"))
      (node (ref "OUTL") (pin "2") (pinfunction "S_2") (pintype "passive"))
      (node (ref "R9") (pin "1") (pinfunction "1_1") (pintype "passive"))
    )
    (net (code "48") (name "Net-(OA3-ON1)") (class "Default")
      (node (ref "OA3") (pin "1") (pinfunction "ON1_1") (pintype "passive"))
      (node (ref "P1") (pin "A") (pinfunction "A_A") (pintype "passive"))
    )
    (net (code "49") (name "Net-(OA3-ON2)") (class "Default")
      (node (ref "OA3") (pin "5") (pinfunction "ON2_5") (pintype "passive"))
      (node (ref "P1") (pin "E") (pinfunction "E_E") (pintype "passive"))
    )
    (net (code "50") (name "Net-(OA3-OUT)") (class "Default")
      (node (ref "C13") (pin "1") (pinfunction "1_1") (pintype "passive"))
      (node (ref "OA3") (pin "6") (pinfunction "OUT_6") (pintype "output"))
      (node (ref "R11") (pin "2") (pinfunction "2_2") (pintype "passive"))
    )
    (net (code "51") (name "Net-(OA201-+IN)") (class "Default")
      (node (ref "C206") (pin "2") (pinfunction "2_2") (pintype "passive"))
      (node (ref "C206") (pin "3") (pinfunction "3_3") (pintype "passive"))
      (node (ref "OA201") (pin "3") (pinfunction "+IN_3") (pintype "input"))
      (node (ref "R211") (pin "1") (pinfunction "1_1") (pintype "passive"))
    )
    (net (code "52") (name "Net-(OA201--IN)") (class "Default")
      (node (ref "C207") (pin "1") (pinfunction "1_1") (pintype "passive"))
      (node (ref "OA201") (pin "2") (pinfunction "-IN_2") (pintype "input"))
      (node (ref "R202") (pin "2") (pinfunction "2_2") (pintype "passive"))
      (node (ref "R203") (pin "1") (pinfunction "1_1") (pintype "passive"))
    )
    (net (code "53") (name "Net-(OA201-OUT)") (class "Default")
      (node (ref "C207") (pin "2") (pinfunction "2_2") (pintype "passive"))
      (node (ref "OA201") (pin "6") (pinfunction "OUT_6") (pintype "output"))
      (node (ref "R203") (pin "2") (pinfunction "2_2") (pintype "passive"))
      (node (ref "R204") (pin "1") (pinfunction "1_1") (pintype "passive"))
      (node (ref "R205") (pin "1") (pinfunction "1_1") (pintype "passive"))
      (node (ref "R210") (pin "1") (pinfunction "1_1") (pintype "passive"))
    )
    (net (code "54") (name "Net-(OA202-+IN)") (class "Default")
      (node (ref "C209") (pin "2") (pinfunction "2_2") (pintype "passive"))
      (node (ref "OA202") (pin "3") (pinfunction "+IN_3") (pintype "input"))
      (node (ref "R204") (pin "2") (pinfunction "2_2") (pintype "passive"))
    )
    (net (code "55") (name "Net-(OA202--IN)") (class "Default")
      (node (ref "JP201") (pin "2") (pinfunction "2_2") (pintype "passive"))
      (node (ref "OA202") (pin "2") (pinfunction "-IN_2") (pintype "input"))
    )
    (net (code "56") (name "Net-(OA202-OUT)") (class "Default")
      (node (ref "C211") (pin "1") (pinfunction "1_1") (pintype "passive"))
      (node (ref "OA202") (pin "6") (pinfunction "OUT_6") (pintype "output"))
      (node (ref "OUTR") (pin "1") (pinfunction "S_1") (pintype "passive"))
      (node (ref "R209") (pin "1") (pinfunction "1_1") (pintype "passive"))
    )
    (net (code "57") (name "Net-(OA203-ON1)") (class "Default")
      (node (ref "OA203") (pin "1") (pinfunction "ON1_1") (pintype "passive"))
      (node (ref "P201") (pin "A") (pinfunction "A_A") (pintype "passive"))
    )
    (net (code "58") (name "Net-(OA203-ON2)") (class "Default")
      (node (ref "OA203") (pin "5") (pinfunction "ON2_5") (pintype "passive"))
      (node (ref "P201") (pin "E") (pinfunction "E_E") (pintype "passive"))
    )
    (net (code "59") (name "Net-(OA203-OUT)") (class "Default")
      (node (ref "C213") (pin "1") (pinfunction "1_1") (pintype "passive"))
      (node (ref "OA203") (pin "6") (pinfunction "OUT_6") (pintype "output"))
      (node (ref "R211") (pin "2") (pinfunction "2_2") (pintype "passive"))
    )
    (net (code "60") (name "Net-(T3-B)") (class "Default")
      (node (ref "R30") (pin "2") (pinfunction "2_2") (pintype "passive"))
      (node (ref "T3") (pin "2") (pinfunction "B_2") (pintype "passive"))
    )
    (net (code "61") (name "Net-(T3-C)") (class "Default")
      (node (ref "R29") (pin "1") (pinfunction "1_1") (pintype "passive"))
      (node (ref "T3") (pin "3") (pinfunction "C_3") (pintype "passive"))
    )
    (net (code "62") (name "Net-(T4-B)") (class "Default")
      (node (ref "R33") (pin "2") (pinfunction "2_2") (pintype "passive"))
      (node (ref "T4") (pin "2") (pinfunction "B_2") (pintype "passive"))
    )
    (net (code "63") (name "Net-(T4-C)") (class "Default")
      (node (ref "R32") (pin "1") (pinfunction "1_1") (pintype "passive"))
      (node (ref "T4") (pin "3") (pinfunction "C_3") (pintype "passive"))
    )
    (net (code "64") (name "Net-(T203-B)") (class "Default")
      (node (ref "R230") (pin "2") (pinfunction "2_2") (pintype "passive"))
      (node (ref "T203") (pin "2") (pinfunction "B_2") (pintype "passive"))
    )
    (net (code "65") (name "Net-(T203-C)") (class "Default")
      (node (ref "R229") (pin "1") (pinfunction "1_1") (pintype "passive"))
      (node (ref "T203") (pin "3") (pinfunction "C_3") (pintype "passive"))
    )
    (net (code "66") (name "Net-(T204-B)") (class "Default")
      (node (ref "R233") (pin "2") (pinfunction "2_2") (pintype "passive"))
      (node (ref "T204") (pin "2") (pinfunction "B_2") (pintype "passive"))
    )
    (net (code "67") (name "Net-(T204-C)") (class "Default")
      (node (ref "R232") (pin "1") (pinfunction "1_1") (pintype "passive"))
      (node (ref "T204") (pin "3") (pinfunction "C_3") (pintype "passive"))
    )
    (net (code "68") (name "Net-(~18VA-KL)") (class "Default")
      (node (ref "C101") (pin "2") (pinfunction "2_2") (pintype "passive"))
      (node (ref "C102") (pin "2") (pinfunction "2_2") (pintype "passive"))
      (node (ref "U1") (pin "3") (pinfunction "3_3") (pintype "passive"))
      (node (ref "~18V") (pin "1") (pinfunction "KL_1") (pintype "passive"))
    )
    (net (code "69") (name "Net-(~18VC-KL)") (class "Default")
      (node (ref "C103") (pin "1") (pinfunction "1_1") (pintype "passive"))
      (node (ref "C104") (pin "1") (pinfunction "1_1") (pintype "passive"))
      (node (ref "U1") (pin "4") (pinfunction "4_4") (pintype "passive"))
      (node (ref "~18V") (pin "3") (pinfunction "KL_3") (pintype "passive"))
    )
    (net (code "70") (name "unconnected-(OA1-CMP-Pad5)") (class "Default")
      (node (ref "OA1") (pin "5") (pinfunction "CMP_5") (pintype "passive"))
    )
    (net (code "71") (name "unconnected-(OA1-ON-Pad1)") (class "Default")
      (node (ref "OA1") (pin "1") (pinfunction "ON_1") (pintype "passive"))
    )
    (net (code "72") (name "unconnected-(OA1-ON{slash}CMP-Pad8)") (class "Default")
      (node (ref "OA1") (pin "8") (pinfunction "ON/CMP_8") (pintype "passive"))
    )
    (net (code "73") (name "unconnected-(OA2-CMP-Pad5)") (class "Default")
      (node (ref "OA2") (pin "5") (pinfunction "CMP_5") (pintype "passive"))
    )
    (net (code "74") (name "unconnected-(OA2-ON-Pad1)") (class "Default")
      (node (ref "OA2") (pin "1") (pinfunction "ON_1") (pintype "passive"))
    )
    (net (code "75") (name "unconnected-(OA2-ON{slash}CMP-Pad8)") (class "Default")
      (node (ref "OA2") (pin "8") (pinfunction "ON/CMP_8") (pintype "passive"))
    )
    (net (code "76") (name "unconnected-(OA3-OPT-Pad8)") (class "Default")
      (node (ref "OA3") (pin "8") (pinfunction "OPT_8") (pintype "passive"))
    )
    (net (code "77") (name "unconnected-(OA201-CMP-Pad5)") (class "Default")
      (node (ref "OA201") (pin "5") (pinfunction "CMP_5") (pintype "passive"))
    )
    (net (code "78") (name "unconnected-(OA201-ON-Pad1)") (class "Default")
      (node (ref "OA201") (pin "1") (pinfunction "ON_1") (pintype "passive"))
    )
    (net (code "79") (name "unconnected-(OA201-ON{slash}CMP-Pad8)") (class "Default")
      (node (ref "OA201") (pin "8") (pinfunction "ON/CMP_8") (pintype "passive"))
    )
    (net (code "80") (name "unconnected-(OA202-CMP-Pad5)") (class "Default")
      (node (ref "OA202") (pin "5") (pinfunction "CMP_5") (pintype "passive"))
    )
    (net (code "81") (name "unconnected-(OA202-ON-Pad1)") (class "Default")
      (node (ref "OA202") (pin "1") (pinfunction "ON_1") (pintype "passive"))
    )
    (net (code "82") (name "unconnected-(OA202-ON{slash}CMP-Pad8)") (class "Default")
      (node (ref "OA202") (pin "8") (pinfunction "ON/CMP_8") (pintype "passive"))
    )
    (net (code "83") (name "unconnected-(OA203-OPT-Pad8)") (class "Default")
      (node (ref "OA203") (pin "8") (pinfunction "OPT_8") (pintype "passive"))
    )
  )
)
